# PowerInFilter.net
KiCad netlist of a schematic drawn in Altium Designer
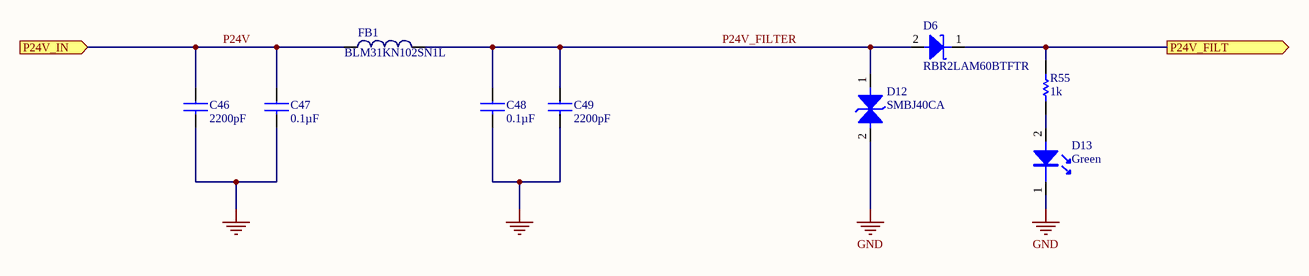
[diagram p0: PowerInFilter.SchDoc]

(export (version "E")
  (design (tool "Eeschema 10.0.6"))
  (components
    (comp (ref "C46")
      (value "2200pF")
      (footprint "C0805")
      (description "CAP CER 2200PF 50V 10% X7R 0805")
      (fields (field (name "MPN") "08055C222KAT2A"))
      (libsource (lib "Capacitor") (part "08055C222KAT2A"))
    )
    (comp (ref "C47")
      (value "0.1µF")
      (footprint "C0805")
      (description "CAP CER 0.1UF 100V X7R 0805")
      (fields (field (name "MPN") "GCM21BR72A104KA37L"))
      (libsource (lib "Capacitor") (part "GCM21BR72A104KA37L"))
    )
    (comp (ref "C48")
      (value "0.1µF")
      (footprint "C0805")
      (description "CAP CER 0.1UF 100V X7R 0805")
      (fields (field (name "MPN") "GCM21BR72A104KA37L"))
      (libsource (lib "Capacitor") (part "GCM21BR72A104KA37L"))
    )
    (comp (ref "C49")
      (value "2200pF")
      (footprint "C0805")
      (description "CAP CER 2200PF 50V 10% X7R 0805")
      (fields (field (name "MPN") "08055C222KAT2A"))
      (libsource (lib "Capacitor") (part "08055C222KAT2A"))
    )
    (comp (ref "D6")
      (value "RBR2LAM60BTFTR")
      (footprint "SOD128")
      (description "AUTOMOTIVE SCHOTTKY BARRIER DIOD")
      (libsource (lib "Diode") (part "RBR2LAM60BTFTR"))
    )
    (comp (ref "D12")
      (value "SMBJ40CA")
      (footprint "DO-214AA (SMBJ40CA)")
      (description "TVS DIODE 40VWM 64.5VC DO214AA")
      (libsource (lib "Diode") (part "SMBJ40CA"))
    )
    (comp (ref "D13")
      (value "Green")
      (footprint "LED0402(GREEN)")
      (description "LED GREEN 0402 SMD")
      (fields (field (name "MPN") "LNJ347W83RA"))
      (libsource (lib "Diode") (part "LNJ347W83RA"))
    )
    (comp (ref "FB1")
      (value "BLM31KN102SN1L")
      (footprint "1206 INDUCTOR")
      (description "FERRITE BEAD 1 KOHM 1206 1LN")
      (libsource (lib "Inductor") (part "BLM31KN102SN1L"))
    )
    (comp (ref "R55")
      (value "1k")
      (footprint "R0603")
      (description "RES SMD 1K OHM 1% 1/10W 0603")
      (fields (field (name "MPN") "ERJ-3EKF1001V"))
      (libsource (lib "Res") (part "ERJ-3EKF1001V"))
    )
  )
  (nets
    (net (code "1") (name "/P24V") (class "Default")
      (node (ref "C46") (pin "1") (pinfunction "1_1") (pintype "passive"))
      (node (ref "C47") (pin "1") (pinfunction "1_1") (pintype "passive"))
      (node (ref "FB1") (pin "2") (pinfunction "2_2") (pintype "passive"))
    )
    (net (code "2") (name "/P24V_FILT") (class "Default")
      (node (ref "D6") (pin "1") (pinfunction "cathode_1") (pintype "passive"))
      (node (ref "R55") (pin "2") (pinfunction "2_2") (pintype "passive"))
    )
    (net (code "3") (name "/P24V_FILTER") (class "Default")
      (node (ref "C48") (pin "1") (pinfunction "1_1") (pintype "passive"))
      (node (ref "C49") (pin "1") (pinfunction "1_1") (pintype "passive"))
      (node (ref "D12") (pin "1") (pinfunction "cathode_1") (pintype "passive"))
      (node (ref "D6") (pin "2") (pinfunction "anode_2") (pintype "passive"))
      (node (ref "FB1") (pin "1") (pinfunction "1_1") (pintype "passive"))
    )
    (net (code "4") (name "GND") (class "Default")
      (node (ref "C46") (pin "2") (pinfunction "2_2") (pintype "passive"))
      (node (ref "C47") (pin "2") (pinfunction "2_2") (pintype "passive"))
      (node (ref "C48") (pin "2") (pinfunction "2_2") (pintype "passive"))
      (node (ref "C49") (pin "2") (pinfunction "2_2") (pintype "passive"))
      (node (ref "D12") (pin "2") (pinfunction "anode_2") (pintype "passive"))
      (node (ref "D13") (pin "1") (pinfunction "1_1") (pintype "passive"))
    )
    (net (code "5") (name "Net-(D13-Pad2)") (class "Default")
      (node (ref "D13") (pin "2") (pinfunction "2_2") (pintype "passive"))
      (node (ref "R55") (pin "1") (pinfunction "1_1") (pintype "passive"))
    )
  )
)
